# Sheet_Transmit.net
KiCad netlist of a schematic drawn in Altium Designer
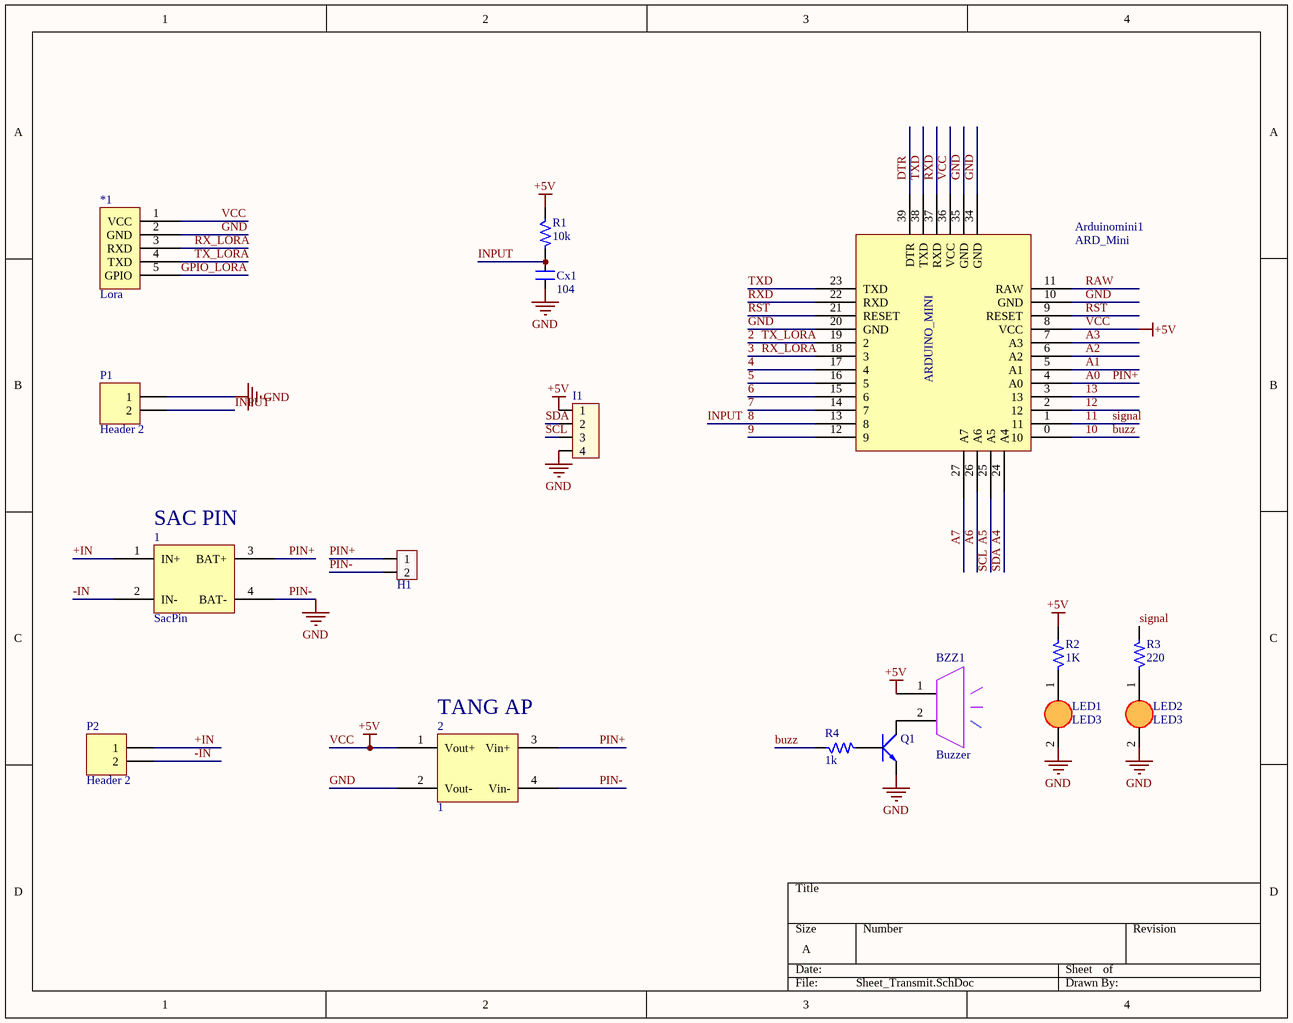
[diagram p0: Sheet_Transmit.SchDoc]

(export (version "E")
  (design (tool "Eeschema 10.0.6"))
  (components
    (comp (ref "*1") (value "Lora") (footprint "Lora") (libsource (lib "Nhan") (part "Lora")))
    (comp (ref "1") (value "SacPin") (footprint "SacPin_TP4056") (libsource (lib "Nhan") (part "SacPin")))
    (comp (ref "2") (value "1") (footprint "TangAp_MT3608") (libsource (lib "Nhan") (part "Tang Ap")))
    (comp (ref "Arduinomini1")
      (value "ARD_Mini")
      (footprint "Arduino_mini")
      (libsource (lib "smart_Home_lib") (part "Arduino_mini"))
    )
    (comp (ref "BZZ1")
      (value "Buzzer")
      (footprint "buzzer 5V")
      (libsource (lib "my Library") (part "Buzzer"))
    )
    (comp (ref "Cx1")
      (value "104")
      (footprint "CN1")
      (description "Cremic For Xtal 1pF => 100pF")
      (libsource (lib "smart_Home_lib") (part "Cap Ceramic"))
    )
    (comp (ref "H1")
      (value "Header2")
      (footprint "Header2")
      (description "Header IDC, 2 x 1 Pin Vertical 2.54mm Pitch (Non-Boxed, Male)")
      (libsource (lib "Library_NEW") (part "Header2"))
    )
    (comp (ref "I1")
      (value "JP4")
      (footprint "CON4")
      (description "Connector 4")
      (libsource (lib "my Library") (part "Con4"))
    )
    (comp (ref "LED1")
      (value "LED3")
      (footprint "LED3mm")
      (description "LED 3mm")
      (libsource (lib "smart_Home_lib") (part "LED 3mm"))
    )
    (comp (ref "LED2")
      (value "LED3")
      (footprint "LED3mm")
      (description "LED 3mm")
      (libsource (lib "smart_Home_lib") (part "LED 3mm"))
    )
    (comp (ref "P1")
      (value "Header 2")
      (footprint "HED2T")
      (description "Header, 2-Pin")
      (fields (field (name "PUBLISHER") "Altium Limited"))
      (libsource (lib "Electric4u") (part "Header 2"))
    )
    (comp (ref "P2")
      (value "Header 2")
      (footprint "HED2T")
      (description "Header, 2-Pin")
      (fields (field (name "PUBLISHER") "Altium Limited"))
      (libsource (lib "Electric4u") (part "Header 2"))
    )
    (comp (ref "Q1")
      (value "C1815")
      (footprint "QTO-92")
      (description "NPN 600mW, ECB")
      (libsource (lib "smart_Home_lib") (part "C1815"))
    )
    (comp (ref "R1")
      (value "10k")
      (footprint "R1/4W")
      (description "Resistor 1/4W")
      (libsource (lib "smart_Home_lib") (part "R"))
    )
    (comp (ref "R2")
      (value "1K")
      (footprint "R1/4W")
      (description "Res")
      (libsource (lib "my Library") (part "Res"))
    )
    (comp (ref "R3")
      (value "220")
      (footprint "R1/4W")
      (description "Res")
      (libsource (lib "my Library") (part "Res"))
    )
    (comp (ref "R4")
      (value "1k")
      (footprint "R1/4W")
      (description "Resistor 1/4W")
      (libsource (lib "smart_Home_lib") (part "R"))
    )
  )
  (nets
    (net (code "1") (name "+5V") (class "Default")
      (node (ref "*1") (pin "1") (pinfunction "VCC_1") (pintype "passive"))
      (node (ref "2") (pin "1") (pinfunction "Vout+_1") (pintype "passive"))
      (node (ref "Arduinomini1") (pin "36") (pinfunction "VCC_36") (pintype "passive"))
      (node (ref "Arduinomini1") (pin "8") (pinfunction "VCC_8") (pintype "passive"))
      (node (ref "BZZ1") (pin "1") (pinfunction "1_1") (pintype "passive"))
      (node (ref "I1") (pin "1") (pinfunction "1_1") (pintype "passive"))
      (node (ref "R1") (pin "1") (pinfunction "1_1") (pintype "passive"))
      (node (ref "R2") (pin "2") (pinfunction "2_2") (pintype "passive"))
    )
    (net (code "2") (name "/+IN") (class "Default")
      (node (ref "1") (pin "1") (pinfunction "IN+_1") (pintype "passive"))
      (node (ref "P2") (pin "1") (pinfunction "1_1") (pintype "passive"))
    )
    (net (code "3") (name "/-IN") (class "Default")
      (node (ref "1") (pin "2") (pinfunction "IN-_2") (pintype "passive"))
      (node (ref "P2") (pin "2") (pinfunction "2_2") (pintype "passive"))
    )
    (net (code "4") (name "/2") (class "Default")
      (node (ref "*1") (pin "4") (pinfunction "TXD_4") (pintype "passive"))
      (node (ref "Arduinomini1") (pin "19") (pinfunction "2_19") (pintype "passive"))
    )
    (net (code "5") (name "/3") (class "Default")
      (node (ref "*1") (pin "3") (pinfunction "RXD_3") (pintype "passive"))
      (node (ref "Arduinomini1") (pin "18") (pinfunction "3_18") (pintype "passive"))
    )
    (net (code "6") (name "/4") (class "Default")
      (node (ref "Arduinomini1") (pin "17") (pinfunction "4_17") (pintype "passive"))
    )
    (net (code "7") (name "/5") (class "Default")
      (node (ref "Arduinomini1") (pin "16") (pinfunction "5_16") (pintype "passive"))
    )
    (net (code "8") (name "/6") (class "Default")
      (node (ref "Arduinomini1") (pin "15") (pinfunction "6_15") (pintype "passive"))
    )
    (net (code "9") (name "/7") (class "Default")
      (node (ref "Arduinomini1") (pin "14") (pinfunction "7_14") (pintype "passive"))
    )
    (net (code "10") (name "/8") (class "Default")
      (node (ref "Arduinomini1") (pin "13") (pinfunction "8_13") (pintype "passive"))
      (node (ref "Cx1") (pin "2") (pinfunction "2_2") (pintype "passive"))
      (node (ref "P1") (pin "2") (pinfunction "2_2") (pintype "passive"))
      (node (ref "R1") (pin "2") (pinfunction "2_2") (pintype "passive"))
    )
    (net (code "11") (name "/9") (class "Default")
      (node (ref "Arduinomini1") (pin "12") (pinfunction "9_12") (pintype "passive"))
    )
    (net (code "12") (name "/10") (class "Default")
      (node (ref "Arduinomini1") (pin "0") (pinfunction "10_0") (pintype "passive"))
      (node (ref "R4") (pin "1") (pinfunction "1_1") (pintype "passive"))
    )
    (net (code "13") (name "/11") (class "Default")
      (node (ref "Arduinomini1") (pin "1") (pinfunction "11_1") (pintype "passive"))
      (node (ref "R3") (pin "2") (pinfunction "2_2") (pintype "passive"))
    )
    (net (code "14") (name "/12") (class "Default")
      (node (ref "Arduinomini1") (pin "2") (pinfunction "12_2") (pintype "passive"))
    )
    (net (code "15") (name "/13") (class "Default")
      (node (ref "Arduinomini1") (pin "3") (pinfunction "13_3") (pintype "passive"))
    )
    (net (code "16") (name "/A0") (class "Default")
      (node (ref "1") (pin "3") (pinfunction "BAT+_3") (pintype "passive"))
      (node (ref "2") (pin "3") (pinfunction "Vin+_3") (pintype "passive"))
      (node (ref "Arduinomini1") (pin "4") (pinfunction "A0_4") (pintype "passive"))
      (node (ref "H1") (pin "1") (pinfunction "1_1") (pintype "passive"))
    )
    (net (code "17") (name "/A1") (class "Default")
      (node (ref "Arduinomini1") (pin "5") (pinfunction "A1_5") (pintype "passive"))
    )
    (net (code "18") (name "/A2") (class "Default")
      (node (ref "Arduinomini1") (pin "6") (pinfunction "A2_6") (pintype "passive"))
    )
    (net (code "19") (name "/A3") (class "Default")
      (node (ref "Arduinomini1") (pin "7") (pinfunction "A3_7") (pintype "passive"))
    )
    (net (code "20") (name "/A4") (class "Default")
      (node (ref "Arduinomini1") (pin "24") (pinfunction "A4_24") (pintype "passive"))
      (node (ref "I1") (pin "2") (pinfunction "2_2") (pintype "passive"))
    )
    (net (code "21") (name "/A5") (class "Default")
      (node (ref "Arduinomini1") (pin "25") (pinfunction "A5_25") (pintype "passive"))
      (node (ref "I1") (pin "3") (pinfunction "3_3") (pintype "passive"))
    )
    (net (code "22") (name "/A6") (class "Default")
      (node (ref "Arduinomini1") (pin "26") (pinfunction "A6_26") (pintype "passive"))
    )
    (net (code "23") (name "/A7") (class "Default")
      (node (ref "Arduinomini1") (pin "27") (pinfunction "A7_27") (pintype "passive"))
    )
    (net (code "24") (name "/DTR") (class "Default")
      (node (ref "Arduinomini1") (pin "39") (pinfunction "DTR_39") (pintype "passive"))
    )
    (net (code "25") (name "/GPIO_LORA") (class "Default")
      (node (ref "*1") (pin "5") (pinfunction "GPIO_5") (pintype "passive"))
    )
    (net (code "26") (name "/RAW") (class "Default")
      (node (ref "Arduinomini1") (pin "11") (pinfunction "RAW_11") (pintype "passive"))
    )
    (net (code "27") (name "/RST") (class "Default")
      (node (ref "Arduinomini1") (pin "21") (pinfunction "RESET_21") (pintype "passive"))
      (node (ref "Arduinomini1") (pin "9") (pinfunction "RESET_9") (pintype "passive"))
    )
    (net (code "28") (name "/RXD") (class "Default")
      (node (ref "Arduinomini1") (pin "22") (pinfunction "RXD_22") (pintype "passive"))
      (node (ref "Arduinomini1") (pin "37") (pinfunction "RXD_37") (pintype "passive"))
    )
    (net (code "29") (name "/TXD") (class "Default")
      (node (ref "Arduinomini1") (pin "23") (pinfunction "TXD_23") (pintype "passive"))
      (node (ref "Arduinomini1") (pin "38") (pinfunction "TXD_38") (pintype "passive"))
    )
    (net (code "30") (name "GND") (class "Default")
      (node (ref "*1") (pin "2") (pinfunction "GND_2") (pintype "passive"))
      (node (ref "1") (pin "4") (pinfunction "BAT-_4") (pintype "passive"))
      (node (ref "2") (pin "2") (pinfunction "Vout-_2") (pintype "passive"))
      (node (ref "2") (pin "4") (pinfunction "Vin-_4") (pintype "passive"))
      (node (ref "Arduinomini1") (pin "10") (pinfunction "GND_10") (pintype "passive"))
      (node (ref "Arduinomini1") (pin "20") (pinfunction "GND_20") (pintype "passive"))
      (node (ref "Arduinomini1") (pin "34") (pinfunction "GND_34") (pintype "passive"))
      (node (ref "Arduinomini1") (pin "35") (pinfunction "GND_35") (pintype "passive"))
      (node (ref "Cx1") (pin "1") (pinfunction "1_1") (pintype "passive"))
      (node (ref "H1") (pin "2") (pinfunction "2_2") (pintype "passive"))
      (node (ref "I1") (pin "4") (pinfunction "4_4") (pintype "passive"))
      (node (ref "LED1") (pin "2") (pinfunction "K_2") (pintype "passive"))
      (node (ref "LED2") (pin "2") (pinfunction "K_2") (pintype "passive"))
      (node (ref "P1") (pin "1") (pinfunction "1_1") (pintype "passive"))
      (node (ref "Q1") (pin "1") (pinfunction "E_1") (pintype "passive"))
    )
    (net (code "31") (name "Net-(LED1-A)") (class "Default")
      (node (ref "LED1") (pin "1") (pinfunction "A_1") (pintype "passive"))
      (node (ref "R2") (pin "1") (pinfunction "1_1") (pintype "passive"))
    )
    (net (code "32") (name "Net-(LED2-A)") (class "Default")
      (node (ref "LED2") (pin "1") (pinfunction "A_1") (pintype "passive"))
      (node (ref "R3") (pin "1") (pinfunction "1_1") (pintype "passive"))
    )
    (net (code "33") (name "Net-(Q1-B)") (class "Default")
      (node (ref "Q1") (pin "3") (pinfunction "B_3") (pintype "passive"))
      (node (ref "R4") (pin "2") (pinfunction "2_2") (pintype "passive"))
    )
    (net (code "34") (name "Net-(Q1-C)") (class "Default")
      (node (ref "BZZ1") (pin "2") (pinfunction "2_2") (pintype "passive"))
      (node (ref "Q1") (pin "2") (pinfunction "C_2") (pintype "passive"))
    )
  )
)
